# Ammeter.net
KiCad netlist of a schematic drawn in EAGLE
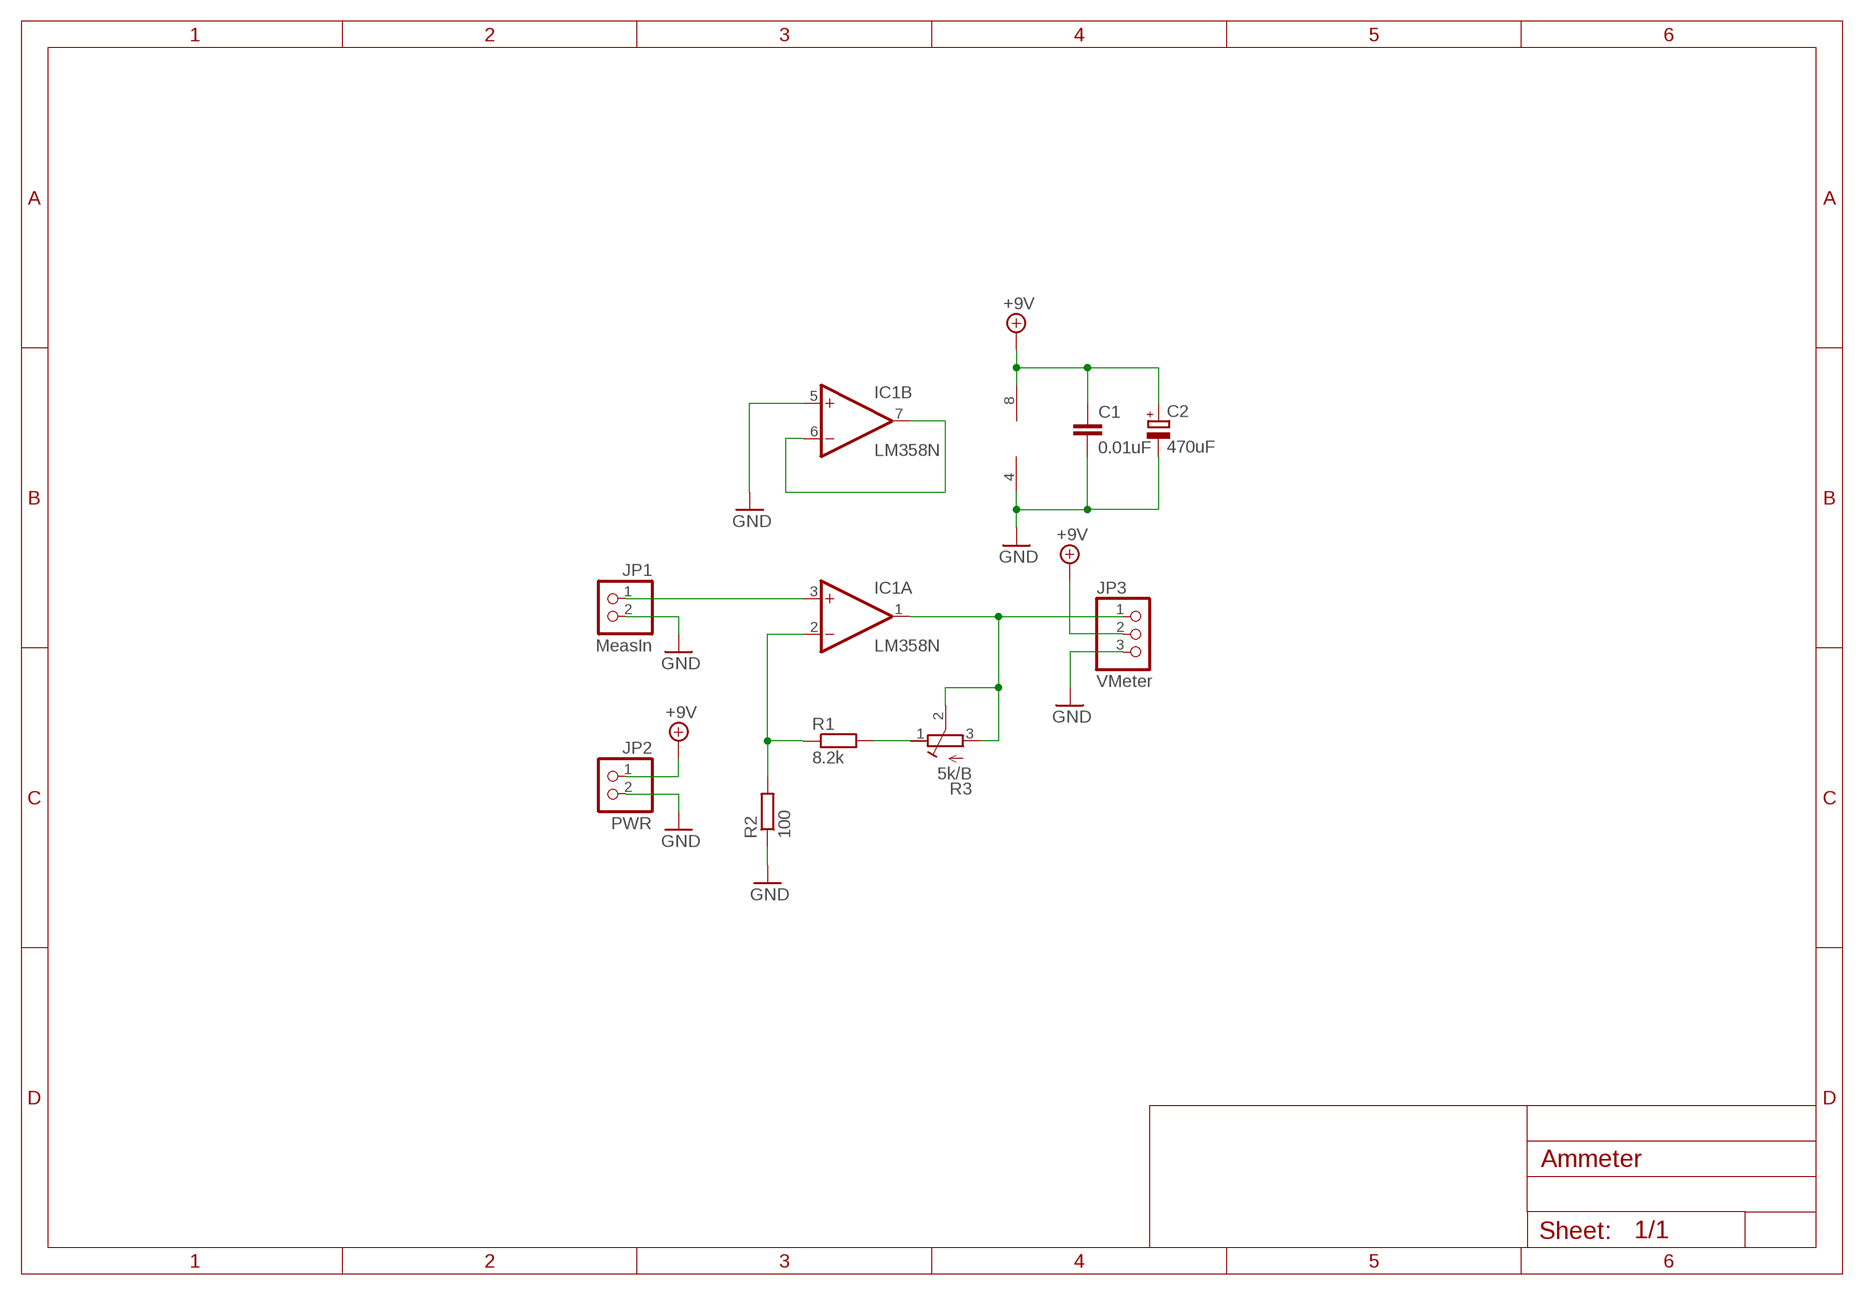
[diagram p0: schematic, sheet 1]

(export (version "E")
  (design (tool "Eeschema 10.0.6"))
  (components
    (comp (ref "C1")
      (value "0.01uF")
      (footprint "eagle-import:C025-024X044")
      (libsource (lib "eagle-import") (part "C-EU025-024X044"))
    )
    (comp (ref "C2")
      (value "470uF")
      (footprint "eagle-import:SANYO-OSCON_F13")
      (libsource (lib "eagle-import") (part "CPOL-EUSANYO_F13"))
    )
    (comp (ref "IC1")
      (value "LM358N")
      (footprint "eagle-import:DIL08")
      (libsource (lib "eagle-import") (part "LM358N"))
    )
    (comp (ref "JP1")
      (value "MeasIn")
      (footprint "eagle-import:1X02")
      (libsource (lib "eagle-import") (part "PINHD-1X2"))
    )
    (comp (ref "JP2")
      (value "PWR")
      (footprint "eagle-import:1X02")
      (libsource (lib "eagle-import") (part "PINHD-1X2"))
    )
    (comp (ref "JP3")
      (value "VMeter")
      (footprint "eagle-import:1X03")
      (libsource (lib "eagle-import") (part "PINHD-1X3"))
    )
    (comp (ref "R1")
      (value "8.2k")
      (footprint "eagle-import:0207_7")
      (libsource (lib "eagle-import") (part "R-EU_0207/7"))
    )
    (comp (ref "R2")
      (value "100")
      (footprint "eagle-import:0207_7")
      (libsource (lib "eagle-import") (part "R-EU_0207/7"))
    )
    (comp (ref "R3")
      (value "5k/B")
      (footprint "eagle-import:RTRIM43P")
      (libsource (lib "eagle-import") (part "R-TRIMM43P"))
    )
  )
  (nets
    (net (code "1") (name "+9V") (class "Default")
      (node (ref "C1") (pin "1") (pinfunction "1_1") (pintype "passive"))
      (node (ref "C2") (pin "+") (pinfunction "+_+") (pintype "passive"))
      (node (ref "IC1") (pin "8") (pinfunction "V+_8") (pintype "power_in"))
      (node (ref "JP2") (pin "1") (pinfunction "1_1") (pintype "passive"))
      (node (ref "JP3") (pin "2") (pinfunction "2_2") (pintype "passive"))
    )
    (net (code "2") (name "GND") (class "Default")
      (node (ref "C1") (pin "2") (pinfunction "2_2") (pintype "passive"))
      (node (ref "C2") (pin "-") (pinfunction "-_-") (pintype "passive"))
      (node (ref "IC1") (pin "4") (pinfunction "V-_4") (pintype "power_in"))
      (node (ref "IC1") (pin "5") (pinfunction "+IN_5") (pintype "input"))
      (node (ref "JP1") (pin "2") (pinfunction "2_2") (pintype "passive"))
      (node (ref "JP2") (pin "2") (pinfunction "2_2") (pintype "passive"))
      (node (ref "JP3") (pin "3") (pinfunction "3_3") (pintype "passive"))
      (node (ref "R2") (pin "1") (pinfunction "1_1") (pintype "passive"))
    )
    (net (code "3") (name "Net-(IC1A-+IN)") (class "Default")
      (node (ref "IC1") (pin "3") (pinfunction "+IN_3") (pintype "input"))
      (node (ref "JP1") (pin "1") (pinfunction "1_1") (pintype "passive"))
    )
    (net (code "4") (name "Net-(IC1A--IN)") (class "Default")
      (node (ref "IC1") (pin "2") (pinfunction "-IN_2") (pintype "input"))
      (node (ref "R1") (pin "1") (pinfunction "1_1") (pintype "passive"))
      (node (ref "R2") (pin "2") (pinfunction "2_2") (pintype "passive"))
    )
    (net (code "5") (name "Net-(IC1A-OUT)") (class "Default")
      (node (ref "IC1") (pin "1") (pinfunction "OUT_1") (pintype "output"))
      (node (ref "JP3") (pin "1") (pinfunction "1_1") (pintype "passive"))
      (node (ref "R3") (pin "2") (pinfunction "S_2") (pintype "passive"))
      (node (ref "R3") (pin "3") (pinfunction "A_3") (pintype "passive"))
    )
    (net (code "6") (name "Net-(IC1B--IN)") (class "Default")
      (node (ref "IC1") (pin "6") (pinfunction "-IN_6") (pintype "input"))
      (node (ref "IC1") (pin "7") (pinfunction "OUT_7") (pintype "output"))
    )
    (net (code "7") (name "Net-(R3-E)") (class "Default")
      (node (ref "R1") (pin "2") (pinfunction "2_2") (pintype "passive"))
      (node (ref "R3") (pin "1") (pinfunction "E_1") (pintype "passive"))
    )
  )
)
